# zcu-sync-control.net
KiCad netlist of a schematic drawn in EAGLE
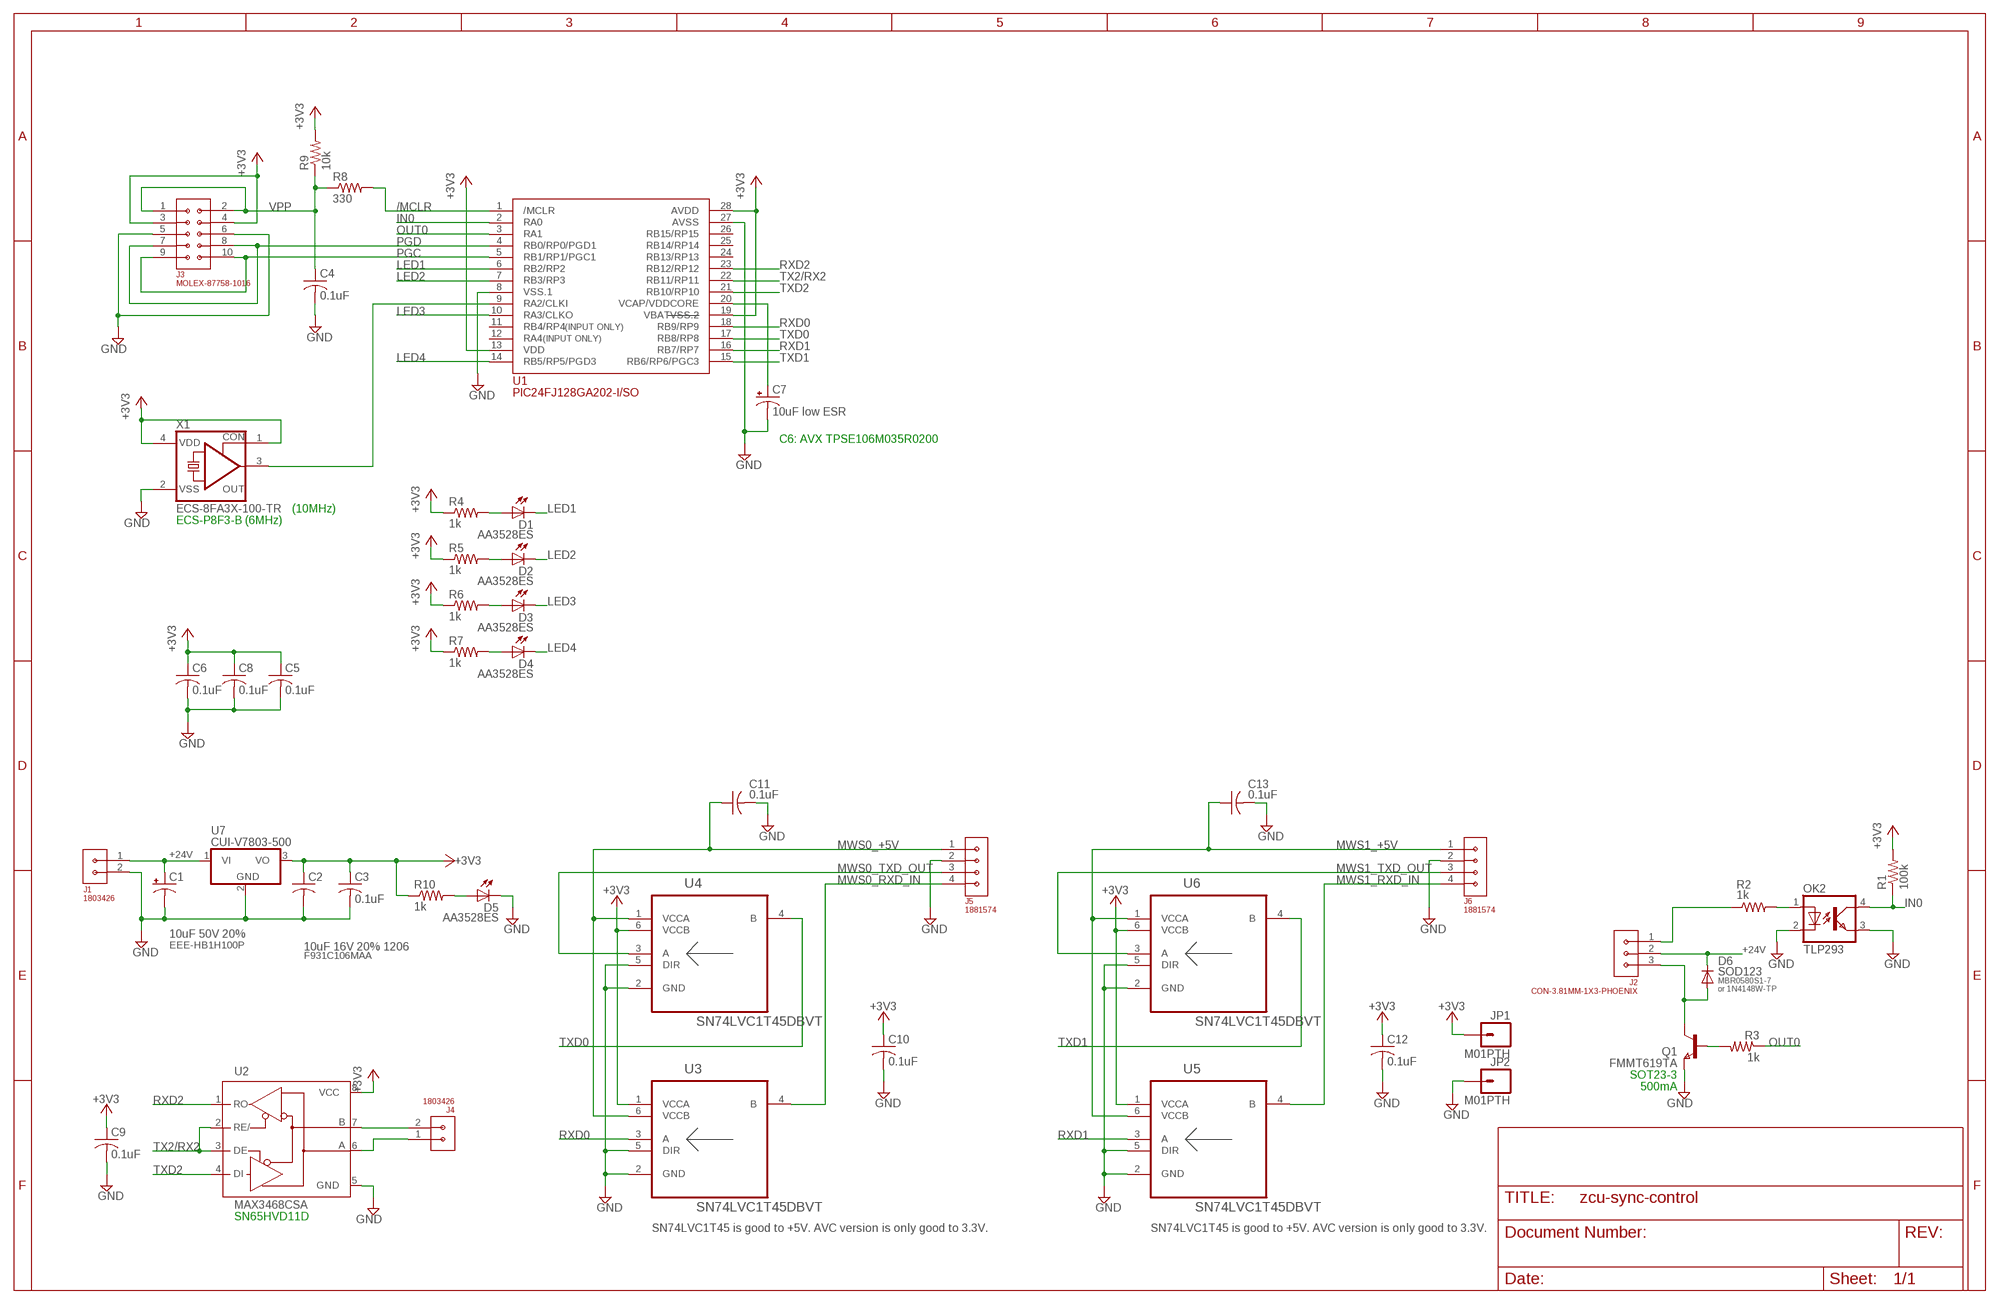
[diagram p0: schematic, sheet 1]

(export (version "E")
  (design (tool "Eeschema 10.0.6"))
  (components
    (comp (ref "C1")
      (value "10uF 50V 20%")
      (footprint "eagle-import:PANASONIC_D")
      (libsource (lib "eagle-import") (part "CPOL-USD"))
    )
    (comp (ref "C2")
      (value "10uF 16V 20% 1206")
      (footprint "eagle-import:C1206")
      (libsource (lib "eagle-import") (part "C-USC1206"))
    )
    (comp (ref "C3")
      (value "0.1uF")
      (footprint "eagle-import:C1206")
      (libsource (lib "eagle-import") (part "C-USC1206"))
    )
    (comp (ref "C4")
      (value "0.1uF")
      (footprint "eagle-import:C1206")
      (libsource (lib "eagle-import") (part "C-USC1206"))
    )
    (comp (ref "C5")
      (value "0.1uF")
      (footprint "eagle-import:C1206")
      (libsource (lib "eagle-import") (part "C-USC1206"))
    )
    (comp (ref "C6")
      (value "0.1uF")
      (footprint "eagle-import:C1206")
      (libsource (lib "eagle-import") (part "C-USC1206"))
    )
    (comp (ref "C7")
      (value "10uF low ESR")
      (footprint "eagle-import:D_7343-31R")
      (libsource (lib "eagle-import") (part "CPOL-USD/7343-31R"))
    )
    (comp (ref "C8")
      (value "0.1uF")
      (footprint "eagle-import:C1206")
      (libsource (lib "eagle-import") (part "C-USC1206"))
    )
    (comp (ref "C9")
      (value "0.1uF")
      (footprint "eagle-import:C1206")
      (libsource (lib "eagle-import") (part "C-USC1206"))
    )
    (comp (ref "C10")
      (value "0.1uF")
      (footprint "eagle-import:C1206")
      (libsource (lib "eagle-import") (part "C-USC1206"))
    )
    (comp (ref "C11")
      (value "0.1uF")
      (footprint "eagle-import:C1206")
      (libsource (lib "eagle-import") (part "C-USC1206"))
    )
    (comp (ref "C12")
      (value "0.1uF")
      (footprint "eagle-import:C1206")
      (libsource (lib "eagle-import") (part "C-USC1206"))
    )
    (comp (ref "C13")
      (value "0.1uF")
      (footprint "eagle-import:C1206")
      (libsource (lib "eagle-import") (part "C-USC1206"))
    )
    (comp (ref "D1")
      (value "AA3528ES")
      (footprint "eagle-import:KA-3528ASYC")
      (libsource (lib "eagle-import") (part "LEDKA-3528ASYC"))
    )
    (comp (ref "D2")
      (value "AA3528ES")
      (footprint "eagle-import:KA-3528ASYC")
      (libsource (lib "eagle-import") (part "LEDKA-3528ASYC"))
    )
    (comp (ref "D3")
      (value "AA3528ES")
      (footprint "eagle-import:KA-3528ASYC")
      (libsource (lib "eagle-import") (part "LEDKA-3528ASYC"))
    )
    (comp (ref "D4")
      (value "AA3528ES")
      (footprint "eagle-import:KA-3528ASYC")
      (libsource (lib "eagle-import") (part "LEDKA-3528ASYC"))
    )
    (comp (ref "D5")
      (value "AA3528ES")
      (footprint "eagle-import:KA-3528ASYC")
      (libsource (lib "eagle-import") (part "LEDKA-3528ASYC"))
    )
    (comp (ref "D6")
      (value "1N4148W-TP")
      (footprint "eagle-import:SOD123")
      (libsource (lib "eagle-import") (part "DIODE-SOD123"))
    )
    (comp (ref "J1")
      (value "1803426")
      (footprint "eagle-import:CON-PHOENIX-1803426-3.81-1X2")
      (libsource (lib "eagle-import") (part "CON-3.81MM-1X2-PHOENIX-1803426"))
    )
    (comp (ref "J2")
      (value "CON-3.81MM-1X3-PHOENIX")
      (footprint "eagle-import:CON-PHOENIX-3.81-1X3")
      (libsource (lib "eagle-import") (part "CON-3.81MM-1X3-PHOENIX"))
    )
    (comp (ref "J3")
      (value "MOLEX-87758-1016")
      (footprint "eagle-import:CON-2MM-2X5")
      (libsource (lib "eagle-import") (part "CON-2MM-2X5-MOLEX-87758-1016"))
    )
    (comp (ref "J4")
      (value "1803426")
      (footprint "eagle-import:CON-PHOENIX-1803426-3.81-1X2")
      (libsource (lib "eagle-import") (part "CON-3.81MM-1X2-PHOENIX-1803426"))
    )
    (comp (ref "J5")
      (value "1881574")
      (footprint "eagle-import:CON-2.5MM-1X4-PHOENIX-1881574")
      (libsource (lib "eagle-import") (part "CON-2.5MM-1X4-PHOENIX-1881574"))
    )
    (comp (ref "J6")
      (value "1881574")
      (footprint "eagle-import:CON-2.5MM-1X4-PHOENIX-1881574")
      (libsource (lib "eagle-import") (part "CON-2.5MM-1X4-PHOENIX-1881574"))
    )
    (comp (ref "JP1")
      (value "M01PTH")
      (footprint "eagle-import:1X01")
      (libsource (lib "eagle-import") (part "M01PTH"))
    )
    (comp (ref "JP2")
      (value "M01PTH")
      (footprint "eagle-import:1X01")
      (libsource (lib "eagle-import") (part "M01PTH"))
    )
    (comp (ref "OK2")
      (value "TLP293")
      (footprint "eagle-import:MINI-FLAT-4")
      (libsource (lib "eagle-import") (part "TLP283"))
    )
    (comp (ref "Q1")
      (value "FMMT619TA")
      (footprint "eagle-import:SOT-23")
      (fields (field (name "MPN") "DSS20201L-7"))
      (libsource (lib "eagle-import") (part "NPNSOT23"))
    )
    (comp (ref "R1")
      (value "100k")
      (footprint "eagle-import:R1206")
      (libsource (lib "eagle-import") (part "R-US_R1206"))
    )
    (comp (ref "R2")
      (value "1k")
      (footprint "eagle-import:R1206")
      (libsource (lib "eagle-import") (part "R-US_R1206"))
    )
    (comp (ref "R3")
      (value "1k")
      (footprint "eagle-import:R1206")
      (libsource (lib "eagle-import") (part "R-US_R1206"))
    )
    (comp (ref "R4")
      (value "1k")
      (footprint "eagle-import:R1206")
      (libsource (lib "eagle-import") (part "R-US_R1206"))
    )
    (comp (ref "R5")
      (value "1k")
      (footprint "eagle-import:R1206")
      (libsource (lib "eagle-import") (part "R-US_R1206"))
    )
    (comp (ref "R6")
      (value "1k")
      (footprint "eagle-import:R1206")
      (libsource (lib "eagle-import") (part "R-US_R1206"))
    )
    (comp (ref "R7")
      (value "1k")
      (footprint "eagle-import:R1206")
      (libsource (lib "eagle-import") (part "R-US_R1206"))
    )
    (comp (ref "R8")
      (value "330")
      (footprint "eagle-import:R1206")
      (libsource (lib "eagle-import") (part "R-US_R1206"))
    )
    (comp (ref "R9")
      (value "10k")
      (footprint "eagle-import:R1206")
      (libsource (lib "eagle-import") (part "R-US_R1206"))
    )
    (comp (ref "R10")
      (value "1k")
      (footprint "eagle-import:R1206")
      (libsource (lib "eagle-import") (part "R-US_R1206"))
    )
    (comp (ref "U1")
      (value "PIC24FJ128GA202-I/SO")
      (footprint "eagle-import:SO28W")
      (libsource (lib "eagle-import") (part "PIC24HJ128GP202-I/SO"))
    )
    (comp (ref "U2")
      (value "MAX3468CSA")
      (footprint "eagle-import:SO08")
      (fields (field (name "MPN") "MAX3468CSA+"))
      (libsource (lib "eagle-import") (part "MAX34SA68C"))
    )
    (comp (ref "U3")
      (value "SN74LVC1T45DBVT")
      (footprint "eagle-import:SOT95P280X145-6N")
      (fields (field (name "MPN") "SN74AVC1T45DBVT"))
      (libsource (lib "eagle-import") (part "SN74AVC1T45DBVT"))
    )
    (comp (ref "U4")
      (value "SN74LVC1T45DBVT")
      (footprint "eagle-import:SOT95P280X145-6N")
      (fields (field (name "MPN") "SN74AVC1T45DBVT"))
      (libsource (lib "eagle-import") (part "SN74AVC1T45DBVT"))
    )
    (comp (ref "U5")
      (value "SN74LVC1T45DBVT")
      (footprint "eagle-import:SOT95P280X145-6N")
      (fields (field (name "MPN") "SN74AVC1T45DBVT"))
      (libsource (lib "eagle-import") (part "SN74AVC1T45DBVT"))
    )
    (comp (ref "U6")
      (value "SN74LVC1T45DBVT")
      (footprint "eagle-import:SOT95P280X145-6N")
      (fields (field (name "MPN") "SN74AVC1T45DBVT"))
      (libsource (lib "eagle-import") (part "SN74AVC1T45DBVT"))
    )
    (comp (ref "U7")
      (value "CUI-V7803-500")
      (footprint "eagle-import:CUI-78XX-500")
      (libsource (lib "eagle-import") (part "CUI-V7803-500"))
    )
    (comp (ref "X1")
      (value "ECS-8FA3X-100-TR")
      (footprint "eagle-import:1100S")
      (libsource (lib "eagle-import") (part "CRYSTAL_RES-1100S"))
    )
  )
  (nets
    (net (code "1") (name "+3V3") (class "Default")
      (node (ref "C10") (pin "1") (pinfunction "1_1") (pintype "passive"))
      (node (ref "C12") (pin "1") (pinfunction "1_1") (pintype "passive"))
      (node (ref "C2") (pin "1") (pinfunction "1_1") (pintype "passive"))
      (node (ref "C3") (pin "1") (pinfunction "1_1") (pintype "passive"))
      (node (ref "C5") (pin "1") (pinfunction "1_1") (pintype "passive"))
      (node (ref "C6") (pin "1") (pinfunction "1_1") (pintype "passive"))
      (node (ref "C8") (pin "1") (pinfunction "1_1") (pintype "passive"))
      (node (ref "C9") (pin "1") (pinfunction "1_1") (pintype "passive"))
      (node (ref "J3") (pin "3") (pinfunction "3_3") (pintype "bidirectional"))
      (node (ref "J3") (pin "4") (pinfunction "4_4") (pintype "bidirectional"))
      (node (ref "JP1") (pin "1") (pinfunction "1_1") (pintype "passive"))
      (node (ref "R1") (pin "2") (pinfunction "2_2") (pintype "passive"))
      (node (ref "R10") (pin "1") (pinfunction "1_1") (pintype "passive"))
      (node (ref "R4") (pin "1") (pinfunction "1_1") (pintype "passive"))
      (node (ref "R5") (pin "1") (pinfunction "1_1") (pintype "passive"))
      (node (ref "R6") (pin "1") (pinfunction "1_1") (pintype "passive"))
      (node (ref "R7") (pin "1") (pinfunction "1_1") (pintype "passive"))
      (node (ref "R9") (pin "2") (pinfunction "2_2") (pintype "passive"))
      (node (ref "U1") (pin "13") (pinfunction "VDD_13") (pintype "bidirectional"))
      (node (ref "U1") (pin "19") (pinfunction "VSS.2_19") (pintype "bidirectional"))
      (node (ref "U1") (pin "28") (pinfunction "AVDD_28") (pintype "bidirectional"))
      (node (ref "U2") (pin "8") (pinfunction "VCC_8") (pintype "power_in"))
      (node (ref "U3") (pin "1") (pinfunction "VCCA_1") (pintype "power_in"))
      (node (ref "U4") (pin "6") (pinfunction "VCCB_6") (pintype "power_in"))
      (node (ref "U5") (pin "1") (pinfunction "VCCA_1") (pintype "power_in"))
      (node (ref "U6") (pin "6") (pinfunction "VCCB_6") (pintype "power_in"))
      (node (ref "U7") (pin "3") (pinfunction "VO_3") (pintype "passive"))
      (node (ref "X1") (pin "1") (pinfunction "CON_1") (pintype "input"))
      (node (ref "X1") (pin "4") (pinfunction "VDD_4") (pintype "power_in"))
    )
    (net (code "2") (name "/+24V") (class "Default")
      (node (ref "C1") (pin "+") (pinfunction "+_+") (pintype "passive"))
      (node (ref "D6") (pin "C") (pinfunction "C_C") (pintype "passive"))
      (node (ref "J1") (pin "1") (pinfunction "1_1") (pintype "bidirectional"))
      (node (ref "J2") (pin "2") (pinfunction "2_2") (pintype "bidirectional"))
      (node (ref "U7") (pin "1") (pinfunction "VI_1") (pintype "input"))
    )
    (net (code "3") (name "/IN0") (class "Default")
      (node (ref "OK2") (pin "4") (pinfunction "COL_4") (pintype "passive"))
      (node (ref "R1") (pin "1") (pinfunction "1_1") (pintype "passive"))
      (node (ref "U1") (pin "2") (pinfunction "RA0_2") (pintype "bidirectional"))
    )
    (net (code "4") (name "/LED1") (class "Default")
      (node (ref "D1") (pin "C") (pinfunction "C_C") (pintype "passive"))
      (node (ref "U1") (pin "6") (pinfunction "RB2/RP2_6") (pintype "bidirectional"))
    )
    (net (code "5") (name "/LED2") (class "Default")
      (node (ref "D2") (pin "C") (pinfunction "C_C") (pintype "passive"))
      (node (ref "U1") (pin "7") (pinfunction "RB3/RP3_7") (pintype "bidirectional"))
    )
    (net (code "6") (name "/LED3") (class "Default")
      (node (ref "D3") (pin "C") (pinfunction "C_C") (pintype "passive"))
      (node (ref "U1") (pin "10") (pinfunction "RA3/CLKO_10") (pintype "bidirectional"))
    )
    (net (code "7") (name "/LED4") (class "Default")
      (node (ref "D4") (pin "C") (pinfunction "C_C") (pintype "passive"))
      (node (ref "U1") (pin "14") (pinfunction "RB5/RP5/PGD3_14") (pintype "bidirectional"))
    )
    (net (code "8") (name "/MWS0_+5V") (class "Default")
      (node (ref "C11") (pin "1") (pinfunction "1_1") (pintype "passive"))
      (node (ref "J5") (pin "1") (pinfunction "1_1") (pintype "bidirectional"))
      (node (ref "U3") (pin "6") (pinfunction "VCCB_6") (pintype "power_in"))
      (node (ref "U4") (pin "1") (pinfunction "VCCA_1") (pintype "power_in"))
    )
    (net (code "9") (name "/MWS0_RXD_IN") (class "Default")
      (node (ref "J5") (pin "4") (pinfunction "4_4") (pintype "bidirectional"))
      (node (ref "U3") (pin "4") (pinfunction "B_4") (pintype "output"))
    )
    (net (code "10") (name "/MWS0_TXD_OUT") (class "Default")
      (node (ref "J5") (pin "3") (pinfunction "3_3") (pintype "bidirectional"))
      (node (ref "U4") (pin "3") (pinfunction "A_3") (pintype "input"))
    )
    (net (code "11") (name "/MWS1_+5V") (class "Default")
      (node (ref "C13") (pin "1") (pinfunction "1_1") (pintype "passive"))
      (node (ref "J6") (pin "1") (pinfunction "1_1") (pintype "bidirectional"))
      (node (ref "U5") (pin "6") (pinfunction "VCCB_6") (pintype "power_in"))
      (node (ref "U6") (pin "1") (pinfunction "VCCA_1") (pintype "power_in"))
    )
    (net (code "12") (name "/MWS1_RXD_IN") (class "Default")
      (node (ref "J6") (pin "4") (pinfunction "4_4") (pintype "bidirectional"))
      (node (ref "U5") (pin "4") (pinfunction "B_4") (pintype "output"))
    )
    (net (code "13") (name "/MWS1_TXD_OUT") (class "Default")
      (node (ref "J6") (pin "3") (pinfunction "3_3") (pintype "bidirectional"))
      (node (ref "U6") (pin "3") (pinfunction "A_3") (pintype "input"))
    )
    (net (code "14") (name "/OUT0") (class "Default")
      (node (ref "R3") (pin "1") (pinfunction "1_1") (pintype "passive"))
      (node (ref "U1") (pin "3") (pinfunction "RA1_3") (pintype "bidirectional"))
    )
    (net (code "15") (name "/PGC") (class "Default")
      (node (ref "J3") (pin "10") (pinfunction "10_10") (pintype "bidirectional"))
      (node (ref "J3") (pin "9") (pinfunction "9_9") (pintype "bidirectional"))
      (node (ref "U1") (pin "5") (pinfunction "RB1/RP1/PGC1_5") (pintype "bidirectional"))
    )
    (net (code "16") (name "/PGD") (class "Default")
      (node (ref "J3") (pin "7") (pinfunction "7_7") (pintype "bidirectional"))
      (node (ref "J3") (pin "8") (pinfunction "8_8") (pintype "bidirectional"))
      (node (ref "U1") (pin "4") (pinfunction "RB0/RP0/PGD1_4") (pintype "bidirectional"))
    )
    (net (code "17") (name "/RXD0") (class "Default")
      (node (ref "U1") (pin "18") (pinfunction "RB9/RP9_18") (pintype "bidirectional"))
      (node (ref "U3") (pin "3") (pinfunction "A_3") (pintype "input"))
    )
    (net (code "18") (name "/RXD1") (class "Default")
      (node (ref "U1") (pin "16") (pinfunction "RB7/RP7_16") (pintype "bidirectional"))
      (node (ref "U5") (pin "3") (pinfunction "A_3") (pintype "input"))
    )
    (net (code "19") (name "/RXD2") (class "Default")
      (node (ref "U1") (pin "23") (pinfunction "RB12/RP12_23") (pintype "bidirectional"))
      (node (ref "U2") (pin "1") (pinfunction "RO_1") (pintype "output"))
    )
    (net (code "20") (name "/TX2{slash}RX2") (class "Default")
      (node (ref "U1") (pin "22") (pinfunction "RB11/RP11_22") (pintype "bidirectional"))
      (node (ref "U2") (pin "2") (pinfunction "RE/_2") (pintype "input"))
      (node (ref "U2") (pin "3") (pinfunction "DE_3") (pintype "input"))
    )
    (net (code "21") (name "/TXD0") (class "Default")
      (node (ref "U1") (pin "17") (pinfunction "RB8/RP8_17") (pintype "bidirectional"))
      (node (ref "U4") (pin "4") (pinfunction "B_4") (pintype "output"))
    )
    (net (code "22") (name "/TXD1") (class "Default")
      (node (ref "U1") (pin "15") (pinfunction "RB6/RP6/PGC3_15") (pintype "bidirectional"))
      (node (ref "U6") (pin "4") (pinfunction "B_4") (pintype "output"))
    )
    (net (code "23") (name "/TXD2") (class "Default")
      (node (ref "U1") (pin "21") (pinfunction "RB10/RP10_21") (pintype "bidirectional"))
      (node (ref "U2") (pin "4") (pinfunction "DI_4") (pintype "input"))
    )
    (net (code "24") (name "/VPP") (class "Default")
      (node (ref "C4") (pin "1") (pinfunction "1_1") (pintype "passive"))
      (node (ref "J3") (pin "1") (pinfunction "1_1") (pintype "bidirectional"))
      (node (ref "J3") (pin "2") (pinfunction "2_2") (pintype "bidirectional"))
      (node (ref "R8") (pin "1") (pinfunction "1_1") (pintype "passive"))
      (node (ref "R9") (pin "1") (pinfunction "1_1") (pintype "passive"))
    )
    (net (code "25") (name "/{slash}MCLR") (class "Default")
      (node (ref "R8") (pin "2") (pinfunction "2_2") (pintype "passive"))
      (node (ref "U1") (pin "1") (pinfunction "/MCLR_1") (pintype "bidirectional"))
    )
    (net (code "26") (name "GND") (class "Default")
      (node (ref "C1") (pin "-") (pinfunction "-_-") (pintype "passive"))
      (node (ref "C10") (pin "2") (pinfunction "2_2") (pintype "passive"))
      (node (ref "C11") (pin "2") (pinfunction "2_2") (pintype "passive"))
      (node (ref "C12") (pin "2") (pinfunction "2_2") (pintype "passive"))
      (node (ref "C13") (pin "2") (pinfunction "2_2") (pintype "passive"))
      (node (ref "C2") (pin "2") (pinfunction "2_2") (pintype "passive"))
      (node (ref "C3") (pin "2") (pinfunction "2_2") (pintype "passive"))
      (node (ref "C4") (pin "2") (pinfunction "2_2") (pintype "passive"))
      (node (ref "C5") (pin "2") (pinfunction "2_2") (pintype "passive"))
      (node (ref "C6") (pin "2") (pinfunction "2_2") (pintype "passive"))
      (node (ref "C7") (pin "-") (pinfunction "-_-") (pintype "passive"))
      (node (ref "C8") (pin "2") (pinfunction "2_2") (pintype "passive"))
      (node (ref "C9") (pin "2") (pinfunction "2_2") (pintype "passive"))
      (node (ref "D5") (pin "C") (pinfunction "C_C") (pintype "passive"))
      (node (ref "J1") (pin "2") (pinfunction "2_2") (pintype "bidirectional"))
      (node (ref "J3") (pin "5") (pinfunction "5_5") (pintype "bidirectional"))
      (node (ref "J3") (pin "6") (pinfunction "6_6") (pintype "bidirectional"))
      (node (ref "J5") (pin "2") (pinfunction "2_2") (pintype "bidirectional"))
      (node (ref "J6") (pin "2") (pinfunction "2_2") (pintype "bidirectional"))
      (node (ref "JP2") (pin "1") (pinfunction "1_1") (pintype "passive"))
      (node (ref "OK2") (pin "2") (pinfunction "C_2") (pintype "passive"))
      (node (ref "OK2") (pin "3") (pinfunction "EMIT_3") (pintype "passive"))
      (node (ref "Q1") (pin "2") (pinfunction "E_2") (pintype "passive"))
      (node (ref "U1") (pin "27") (pinfunction "AVSS_27") (pintype "bidirectional"))
      (node (ref "U1") (pin "8") (pinfunction "VSS.1_8") (pintype "bidirectional"))
      (node (ref "U2") (pin "5") (pinfunction "GND_5") (pintype "power_in"))
      (node (ref "U3") (pin "2") (pinfunction "GND_2") (pintype "passive"))
      (node (ref "U3") (pin "5") (pinfunction "DIR_5") (pintype "input"))
      (node (ref "U4") (pin "2") (pinfunction "GND_2") (pintype "passive"))
      (node (ref "U4") (pin "5") (pinfunction "DIR_5") (pintype "input"))
      (node (ref "U5") (pin "2") (pinfunction "GND_2") (pintype "passive"))
      (node (ref "U5") (pin "5") (pinfunction "DIR_5") (pintype "input"))
      (node (ref "U6") (pin "2") (pinfunction "GND_2") (pintype "passive"))
      (node (ref "U6") (pin "5") (pinfunction "DIR_5") (pintype "input"))
      (node (ref "U7") (pin "2") (pinfunction "GND_2") (pintype "passive"))
      (node (ref "X1") (pin "2") (pinfunction "VSS_2") (pintype "power_in"))
    )
    (net (code "27") (name "Net-(D1-PadA)") (class "Default")
      (node (ref "D1") (pin "A") (pinfunction "A_A") (pintype "passive"))
      (node (ref "R4") (pin "2") (pinfunction "2_2") (pintype "passive"))
    )
    (net (code "28") (name "Net-(D2-PadA)") (class "Default")
      (node (ref "D2") (pin "A") (pinfunction "A_A") (pintype "passive"))
      (node (ref "R5") (pin "2") (pinfunction "2_2") (pintype "passive"))
    )
    (net (code "29") (name "Net-(D3-PadA)") (class "Default")
      (node (ref "D3") (pin "A") (pinfunction "A_A") (pintype "passive"))
      (node (ref "R6") (pin "2") (pinfunction "2_2") (pintype "passive"))
    )
    (net (code "30") (name "Net-(D4-PadA)") (class "Default")
      (node (ref "D4") (pin "A") (pinfunction "A_A") (pintype "passive"))
      (node (ref "R7") (pin "2") (pinfunction "2_2") (pintype "passive"))
    )
    (net (code "31") (name "Net-(D5-PadA)") (class "Default")
      (node (ref "D5") (pin "A") (pinfunction "A_A") (pintype "passive"))
      (node (ref "R10") (pin "2") (pinfunction "2_2") (pintype "passive"))
    )
    (net (code "32") (name "Net-(J2-Pad1)") (class "Default")
      (node (ref "J2") (pin "1") (pinfunction "1_1") (pintype "bidirectional"))
      (node (ref "R2") (pin "1") (pinfunction "1_1") (pintype "passive"))
    )
    (net (code "33") (name "Net-(OK2-A)") (class "Default")
      (node (ref "OK2") (pin "1") (pinfunction "A_1") (pintype "passive"))
      (node (ref "R2") (pin "2") (pinfunction "2_2") (pintype "passive"))
    )
    (net (code "34") (name "Net-(Q1-B)") (class "Default")
      (node (ref "Q1") (pin "3") (pinfunction "B_3") (pintype "passive"))
      (node (ref "R3") (pin "2") (pinfunction "2_2") (pintype "passive"))
    )
    (net (code "35") (name "Net-(Q1-C)") (class "Default")
      (node (ref "D6") (pin "A") (pinfunction "A_A") (pintype "passive"))
      (node (ref "J2") (pin "3") (pinfunction "3_3") (pintype "bidirectional"))
      (node (ref "Q1") (pin "1") (pinfunction "C_1") (pintype "passive"))
    )
    (net (code "36") (name "Net-(U1-RA2{slash}CLKI)") (class "Default")
      (node (ref "U1") (pin "9") (pinfunction "RA2/CLKI_9") (pintype "bidirectional"))
      (node (ref "X1") (pin "3") (pinfunction "OUT_3") (pintype "output"))
    )
    (net (code "37") (name "Net-(U1-VCAP{slash}VDDCORE)") (class "Default")
      (node (ref "C7") (pin "+") (pinfunction "+_+") (pintype "passive"))
      (node (ref "U1") (pin "20") (pinfunction "VCAP/VDDCORE_20") (pintype "bidirectional"))
    )
    (net (code "38") (name "Net-(U2-A)") (class "Default")
      (node (ref "J4") (pin "1") (pinfunction "1_1") (pintype "bidirectional"))
      (node (ref "U2") (pin "6") (pinfunction "A_6") (pintype "passive"))
    )
    (net (code "39") (name "Net-(U2-B)") (class "Default")
      (node (ref "J4") (pin "2") (pinfunction "2_2") (pintype "bidirectional"))
      (node (ref "U2") (pin "7") (pinfunction "B_7") (pintype "passive"))
    )
    (net (code "40") (name "unconnected-(U1-RA4-Pad12)") (class "Default")
      (node (ref "U1") (pin "12") (pinfunction "RA4_12") (pintype "bidirectional"))
    )
    (net (code "41") (name "unconnected-(U1-RB4{slash}RP4-Pad11)") (class "Default")
      (node (ref "U1") (pin "11") (pinfunction "RB4/RP4_11") (pintype "bidirectional"))
    )
    (net (code "42") (name "unconnected-(U1-RB13{slash}RP13-Pad24)") (class "Default")
      (node (ref "U1") (pin "24") (pinfunction "RB13/RP13_24") (pintype "bidirectional"))
    )
    (net (code "43") (name "unconnected-(U1-RB14{slash}RP14-Pad25)") (class "Default")
      (node (ref "U1") (pin "25") (pinfunction "RB14/RP14_25") (pintype "bidirectional"))
    )
    (net (code "44") (name "unconnected-(U1-RB15{slash}RP15-Pad26)") (class "Default")
      (node (ref "U1") (pin "26") (pinfunction "RB15/RP15_26") (pintype "bidirectional"))
    )
  )
)
